# SCH1.net
KiCad netlist of a schematic drawn in EAGLE
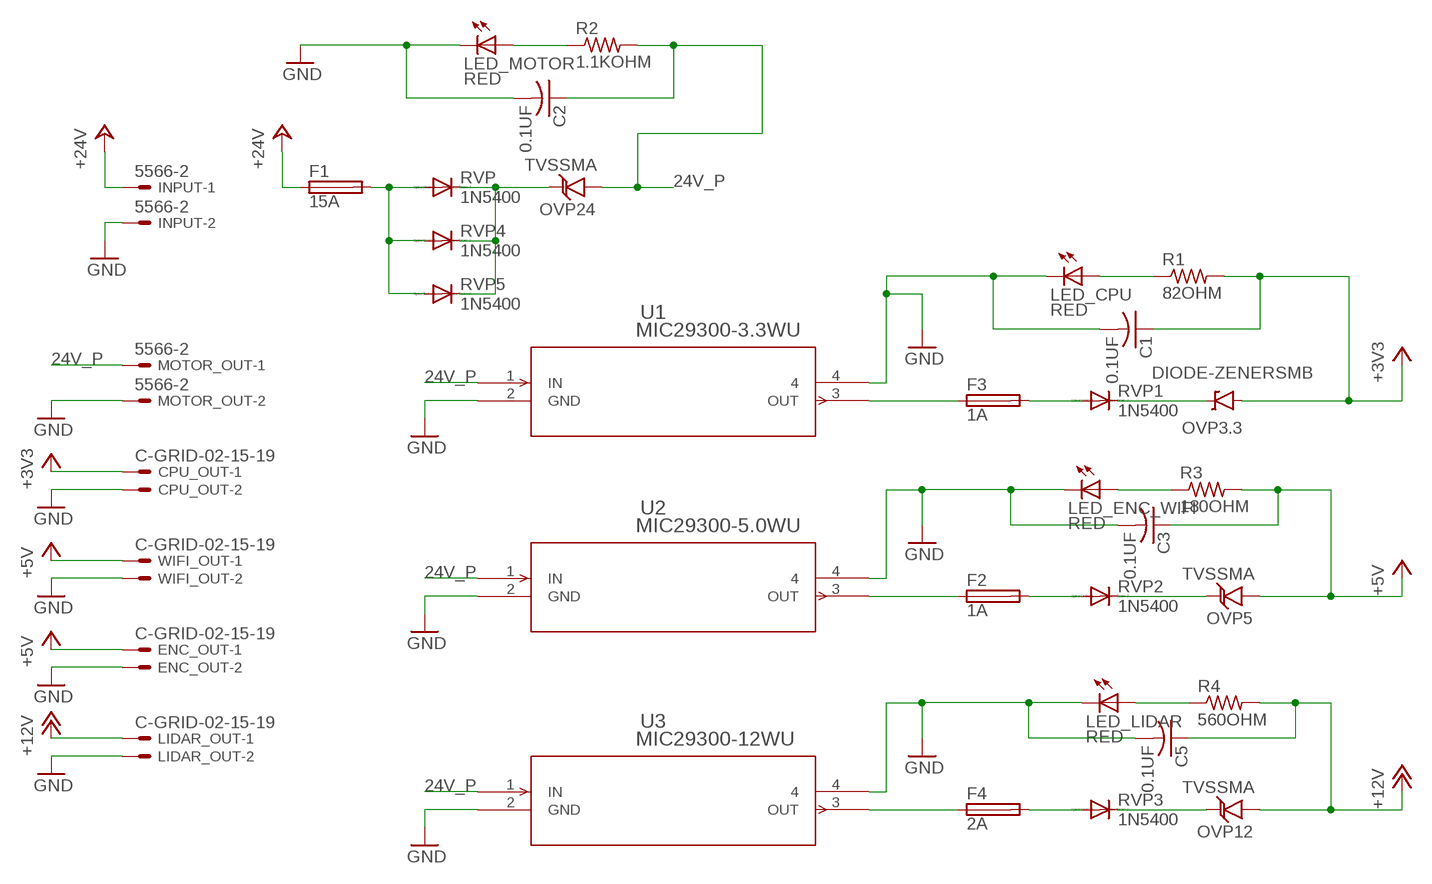
[diagram p0: schematic, sheet 1]

(export (version "E")
  (design (tool "Eeschema 10.0.6"))
  (components
    (comp (ref "C1")
      (value "0.1UF")
      (footprint "eagle-import:C1206")
      (libsource (lib "eagle-import") (part "C-USC1206"))
    )
    (comp (ref "C2")
      (value "0.1UF")
      (footprint "eagle-import:C1206")
      (libsource (lib "eagle-import") (part "C-USC1206"))
    )
    (comp (ref "C3")
      (value "0.1UF")
      (footprint "eagle-import:C1206")
      (libsource (lib "eagle-import") (part "C-USC1206"))
    )
    (comp (ref "C5")
      (value "0.1UF")
      (footprint "eagle-import:C1206")
      (libsource (lib "eagle-import") (part "C-USC1206"))
    )
    (comp (ref "CPU_OUT")
      (value "C-GRID-02-15-19")
      (footprint "eagle-import:15-91-02")
      (libsource (lib "eagle-import") (part "C-GRID-02-15-19"))
    )
    (comp (ref "ENC_OUT")
      (value "C-GRID-02-15-19")
      (footprint "eagle-import:15-91-02")
      (libsource (lib "eagle-import") (part "C-GRID-02-15-19"))
    )
    (comp (ref "F1")
      (value "15A")
      (footprint "eagle-import:TE5")
      (libsource (lib "eagle-import") (part "TE5"))
    )
    (comp (ref "F2")
      (value "1A")
      (footprint "eagle-import:TE5")
      (libsource (lib "eagle-import") (part "TE5"))
    )
    (comp (ref "F3")
      (value "1A")
      (footprint "eagle-import:TE5")
      (libsource (lib "eagle-import") (part "TE5"))
    )
    (comp (ref "F4")
      (value "2A")
      (footprint "eagle-import:TE5")
      (libsource (lib "eagle-import") (part "TE5"))
    )
    (comp (ref "INPUT")
      (value "5566-2")
      (footprint "eagle-import:5566-2")
      (libsource (lib "eagle-import") (part "5566-2"))
    )
    (comp (ref "LED_CPU")
      (value "RED")
      (footprint "eagle-import:1206")
      (libsource (lib "eagle-import") (part "LEDSMT1206"))
    )
    (comp (ref "LED_ENC_WIFI")
      (value "RED")
      (footprint "eagle-import:1206")
      (libsource (lib "eagle-import") (part "LEDSMT1206"))
    )
    (comp (ref "LED_LIDAR")
      (value "RED")
      (footprint "eagle-import:1206")
      (libsource (lib "eagle-import") (part "LEDSMT1206"))
    )
    (comp (ref "LED_MOTOR")
      (value "RED")
      (footprint "eagle-import:1206")
      (libsource (lib "eagle-import") (part "LEDSMT1206"))
    )
    (comp (ref "LIDAR_OUT")
      (value "C-GRID-02-15-19")
      (footprint "eagle-import:15-91-02")
      (libsource (lib "eagle-import") (part "C-GRID-02-15-19"))
    )
    (comp (ref "MOTOR_OUT")
      (value "5566-2")
      (footprint "eagle-import:5566-2")
      (libsource (lib "eagle-import") (part "5566-2"))
    )
    (comp (ref "OVP3.3")
      (value "DIODE-ZENERSMB")
      (footprint "eagle-import:SMB-DIODE")
      (libsource (lib "eagle-import") (part "DIODE-ZENERSMB"))
    )
    (comp (ref "OVP5")
      (value "TVSSMA")
      (footprint "eagle-import:SMA-DIODE")
      (libsource (lib "eagle-import") (part "TVSSMA"))
    )
    (comp (ref "OVP12")
      (value "TVSSMA")
      (footprint "eagle-import:SMA-DIODE")
      (libsource (lib "eagle-import") (part "TVSSMA"))
    )
    (comp (ref "OVP24")
      (value "TVSSMA")
      (footprint "eagle-import:SMA-DIODE")
      (libsource (lib "eagle-import") (part "TVSSMA"))
    )
    (comp (ref "R1")
      (value "82OHM")
      (footprint "eagle-import:R1206W")
      (libsource (lib "eagle-import") (part "R-US_R1206W"))
    )
    (comp (ref "R2")
      (value "1.1KOHM")
      (footprint "eagle-import:R1206W")
      (libsource (lib "eagle-import") (part "R-US_R1206W"))
    )
    (comp (ref "R3")
      (value "180OHM")
      (footprint "eagle-import:R1206W")
      (libsource (lib "eagle-import") (part "R-US_R1206W"))
    )
    (comp (ref "R4")
      (value "560OHM")
      (footprint "eagle-import:R1206W")
      (libsource (lib "eagle-import") (part "R-US_R1206W"))
    )
    (comp (ref "RVP")
      (value "1N5400")
      (footprint "eagle-import:DO201-15")
      (libsource (lib "eagle-import") (part "1N5400"))
    )
    (comp (ref "RVP1")
      (value "1N5400")
      (footprint "eagle-import:DO201-15")
      (libsource (lib "eagle-import") (part "1N5400"))
    )
    (comp (ref "RVP2")
      (value "1N5400")
      (footprint "eagle-import:DO201-15")
      (libsource (lib "eagle-import") (part "1N5400"))
    )
    (comp (ref "RVP3")
      (value "1N5400")
      (footprint "eagle-import:DO201-15")
      (libsource (lib "eagle-import") (part "1N5400"))
    )
    (comp (ref "RVP4")
      (value "1N5400")
      (footprint "eagle-import:DO201-15")
      (libsource (lib "eagle-import") (part "1N5400"))
    )
    (comp (ref "RVP5")
      (value "1N5400")
      (footprint "eagle-import:DO201-15")
      (libsource (lib "eagle-import") (part "1N5400"))
    )
    (comp (ref "U1")
      (value "MIC29300-3.3WU")
      (footprint "eagle-import:TO-263-3")
      (fields
        (field (name "MANUFACTURER_PART_NUMBER") "mic29300-3.3wu")
        (field (name "COPYRIGHT") "Copyright (C) 2015 Accelerated Designs. All rights reserved")
      )
      (libsource (lib "eagle-import") (part "MIC29300-3.3WU"))
    )
    (comp (ref "U2")
      (value "MIC29300-5.0WU")
      (footprint "eagle-import:TO-263-3")
      (fields
        (field (name "MANUFACTURER_PART_NUMBER") "mic29300-5.0wu")
        (field (name "COPYRIGHT") "Copyright (C) 2015 Accelerated Designs. All rights reserved")
      )
      (libsource (lib "eagle-import") (part "MIC29300-5.0WU"))
    )
    (comp (ref "U3")
      (value "MIC29300-12WU")
      (footprint "eagle-import:TO-263-3")
      (fields
        (field (name "MANUFACTURER_PART_NUMBER") "mic29300-12wu")
        (field (name "COPYRIGHT") "Copyright (C) 2015 Accelerated Designs. All rights reserved")
      )
      (libsource (lib "eagle-import") (part "MIC29300-12WU"))
    )
    (comp (ref "WIFI_OUT")
      (value "C-GRID-02-15-19")
      (footprint "eagle-import:15-91-02")
      (libsource (lib "eagle-import") (part "C-GRID-02-15-19"))
    )
  )
  (nets
    (net (code "1") (name "+3V3") (class "Default")
      (node (ref "C1") (pin "1") (pinfunction "1_1") (pintype "passive"))
      (node (ref "CPU_OUT") (pin "1") (pinfunction "S_1") (pintype "passive"))
      (node (ref "OVP3.3") (pin "A") (pinfunction "A_A") (pintype "passive"))
      (node (ref "R1") (pin "2") (pinfunction "2_2") (pintype "passive"))
    )
    (net (code "2") (name "+5V") (class "Default")
      (node (ref "C3") (pin "1") (pinfunction "1_1") (pintype "passive"))
      (node (ref "ENC_OUT") (pin "1") (pinfunction "S_1") (pintype "passive"))
      (node (ref "OVP5") (pin "A") (pinfunction "A_A") (pintype "passive"))
      (node (ref "R3") (pin "2") (pinfunction "2_2") (pintype "passive"))
      (node (ref "WIFI_OUT") (pin "1") (pinfunction "S_1") (pintype "passive"))
    )
    (net (code "3") (name "+12V") (class "Default")
      (node (ref "C5") (pin "1") (pinfunction "1_1") (pintype "passive"))
      (node (ref "LIDAR_OUT") (pin "1") (pinfunction "S_1") (pintype "passive"))
      (node (ref "OVP12") (pin "A") (pinfunction "A_A") (pintype "passive"))
      (node (ref "R4") (pin "2") (pinfunction "2_2") (pintype "passive"))
    )
    (net (code "4") (name "+24V") (class "Default")
      (node (ref "F1") (pin "1") (pinfunction "1_1") (pintype "passive"))
      (node (ref "INPUT") (pin "1") (pinfunction "S_1") (pintype "passive"))
    )
    (net (code "5") (name "/24V_P") (class "Default")
      (node (ref "C2") (pin "1") (pinfunction "1_1") (pintype "passive"))
      (node (ref "MOTOR_OUT") (pin "1") (pinfunction "S_1") (pintype "passive"))
      (node (ref "OVP24") (pin "A") (pinfunction "A_A") (pintype "passive"))
      (node (ref "R2") (pin "2") (pinfunction "2_2") (pintype "passive"))
      (node (ref "U1") (pin "1") (pinfunction "IN_1") (pintype "input"))
      (node (ref "U2") (pin "1") (pinfunction "IN_1") (pintype "input"))
      (node (ref "U3") (pin "1") (pinfunction "IN_1") (pintype "input"))
    )
    (net (code "6") (name "GND") (class "Default")
      (node (ref "C1") (pin "2") (pinfunction "2_2") (pintype "passive"))
      (node (ref "C2") (pin "2") (pinfunction "2_2") (pintype "passive"))
      (node (ref "C3") (pin "2") (pinfunction "2_2") (pintype "passive"))
      (node (ref "C5") (pin "2") (pinfunction "2_2") (pintype "passive"))
      (node (ref "CPU_OUT") (pin "2") (pinfunction "S_2") (pintype "passive"))
      (node (ref "ENC_OUT") (pin "2") (pinfunction "S_2") (pintype "passive"))
      (node (ref "INPUT") (pin "2") (pinfunction "S_2") (pintype "passive"))
      (node (ref "LED_CPU") (pin "C") (pinfunction "C_C") (pintype "passive"))
      (node (ref "LED_ENC_WIFI") (pin "C") (pinfunction "C_C") (pintype "passive"))
      (node (ref "LED_LIDAR") (pin "C") (pinfunction "C_C") (pintype "passive"))
      (node (ref "LED_MOTOR") (pin "C") (pinfunction "C_C") (pintype "passive"))
      (node (ref "LIDAR_OUT") (pin "2") (pinfunction "S_2") (pintype "passive"))
      (node (ref "MOTOR_OUT") (pin "2") (pinfunction "S_2") (pintype "passive"))
      (node (ref "U1") (pin "2") (pinfunction "GND_2") (pintype "power_in"))
      (node (ref "U1") (pin "4") (pinfunction "4_4") (pintype "passive"))
      (node (ref "U2") (pin "2") (pinfunction "GND_2") (pintype "power_in"))
      (node (ref "U2") (pin "4") (pinfunction "4_4") (pintype "passive"))
      (node (ref "U3") (pin "2") (pinfunction "GND_2") (pintype "power_in"))
      (node (ref "U3") (pin "4") (pinfunction "4_4") (pintype "passive"))
      (node (ref "WIFI_OUT") (pin "2") (pinfunction "S_2") (pintype "passive"))
    )
    (net (code "7") (name "Net-(F1-Pad2)") (class "Default")
      (node (ref "F1") (pin "2") (pinfunction "2_2") (pintype "passive"))
      (node (ref "RVP") (pin "A") (pinfunction "A_A") (pintype "passive"))
      (node (ref "RVP4") (pin "A") (pinfunction "A_A") (pintype "passive"))
      (node (ref "RVP5") (pin "A") (pinfunction "A_A") (pintype "passive"))
    )
    (net (code "8") (name "Net-(F2-Pad2)") (class "Default")
      (node (ref "F2") (pin "2") (pinfunction "2_2") (pintype "passive"))
      (node (ref "RVP2") (pin "A") (pinfunction "A_A") (pintype "passive"))
    )
    (net (code "9") (name "Net-(F3-Pad2)") (class "Default")
      (node (ref "F3") (pin "2") (pinfunction "2_2") (pintype "passive"))
      (node (ref "RVP1") (pin "A") (pinfunction "A_A") (pintype "passive"))
    )
    (net (code "10") (name "Net-(F4-Pad2)") (class "Default")
      (node (ref "F4") (pin "2") (pinfunction "2_2") (pintype "passive"))
      (node (ref "RVP3") (pin "A") (pinfunction "A_A") (pintype "passive"))
    )
    (net (code "11") (name "Net-(LED_CPU-PadA)") (class "Default")
      (node (ref "LED_CPU") (pin "A") (pinfunction "A_A") (pintype "passive"))
      (node (ref "R1") (pin "1") (pinfunction "1_1") (pintype "passive"))
    )
    (net (code "12") (name "Net-(LED_ENC_WIFI-PadA)") (class "Default")
      (node (ref "LED_ENC_WIFI") (pin "A") (pinfunction "A_A") (pintype "passive"))
      (node (ref "R3") (pin "1") (pinfunction "1_1") (pintype "passive"))
    )
    (net (code "13") (name "Net-(LED_LIDAR-PadA)") (class "Default")
      (node (ref "LED_LIDAR") (pin "A") (pinfunction "A_A") (pintype "passive"))
      (node (ref "R4") (pin "1") (pinfunction "1_1") (pintype "passive"))
    )
    (net (code "14") (name "Net-(LED_MOTOR-PadA)") (class "Default")
      (node (ref "LED_MOTOR") (pin "A") (pinfunction "A_A") (pintype "passive"))
      (node (ref "R2") (pin "1") (pinfunction "1_1") (pintype "passive"))
    )
    (net (code "15") (name "Net-(OVP3.3-PadC)") (class "Default")
      (node (ref "OVP3.3") (pin "C") (pinfunction "C_C") (pintype "passive"))
      (node (ref "RVP1") (pin "C") (pinfunction "C_C") (pintype "passive"))
    )
    (net (code "16") (name "Net-(OVP5-PadC)") (class "Default")
      (node (ref "OVP5") (pin "C") (pinfunction "C_C") (pintype "passive"))
      (node (ref "RVP2") (pin "C") (pinfunction "C_C") (pintype "passive"))
    )
    (net (code "17") (name "Net-(OVP12-PadC)") (class "Default")
      (node (ref "OVP12") (pin "C") (pinfunction "C_C") (pintype "passive"))
      (node (ref "RVP3") (pin "C") (pinfunction "C_C") (pintype "passive"))
    )
    (net (code "18") (name "Net-(OVP24-PadC)") (class "Default")
      (node (ref "OVP24") (pin "C") (pinfunction "C_C") (pintype "passive"))
      (node (ref "RVP") (pin "C") (pinfunction "C_C") (pintype "passive"))
      (node (ref "RVP4") (pin "C") (pinfunction "C_C") (pintype "passive"))
      (node (ref "RVP5") (pin "C") (pinfunction "C_C") (pintype "passive"))
    )
    (net (code "19") (name "Net-(U1-OUT)") (class "Default")
      (node (ref "F3") (pin "1") (pinfunction "1_1") (pintype "passive"))
      (node (ref "U1") (pin "3") (pinfunction "OUT_3") (pintype "output"))
    )
    (net (code "20") (name "Net-(U2-OUT)") (class "Default")
      (node (ref "F2") (pin "1") (pinfunction "1_1") (pintype "passive"))
      (node (ref "U2") (pin "3") (pinfunction "OUT_3") (pintype "output"))
    )
    (net (code "21") (name "Net-(U3-OUT)") (class "Default")
      (node (ref "F4") (pin "1") (pinfunction "1_1") (pintype "passive"))
      (node (ref "U3") (pin "3") (pinfunction "OUT_3") (pintype "output"))
    )
  )
)
